# LDO.net
KiCad netlist of a schematic drawn in Altium Designer
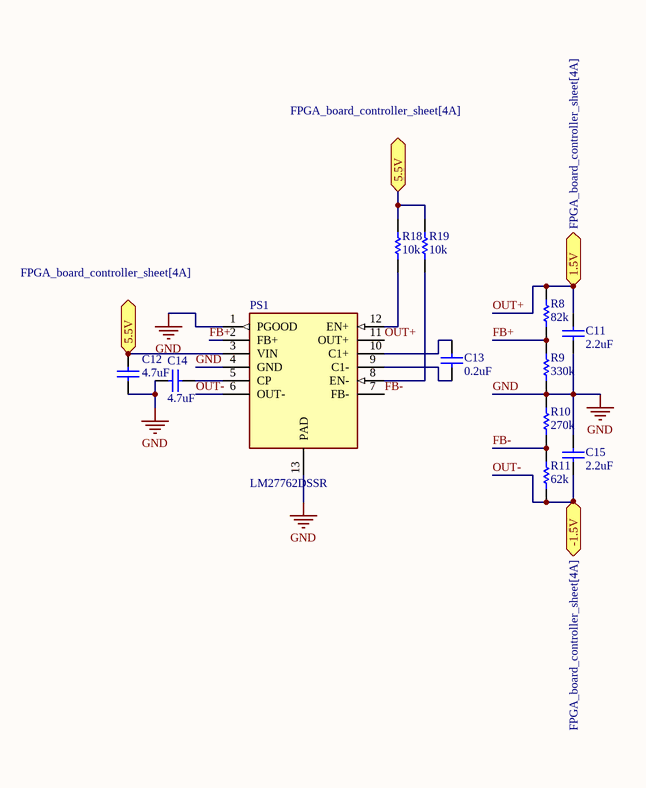
[diagram p0: LDO.SchDoc]

(export (version "E")
  (design (tool "Eeschema 10.0.6"))
  (components
    (comp (ref "C11")
      (value "2.2uF")
      (footprint "C0603")
      (libsource (lib "Schlib_FPGA_Controller") (part "Cap"))
    )
    (comp (ref "C12")
      (value "4.7uF")
      (footprint "C0603")
      (libsource (lib "Schlib_FPGA_Controller") (part "Cap"))
    )
    (comp (ref "C13")
      (value "0.2uF")
      (footprint "C0603")
      (libsource (lib "Schlib_FPGA_Controller") (part "Cap"))
    )
    (comp (ref "C14")
      (value "4.7uF")
      (footprint "C0603")
      (libsource (lib "Schlib_FPGA_Controller") (part "Cap"))
    )
    (comp (ref "C15")
      (value "2.2uF")
      (footprint "C0603")
      (libsource (lib "Schlib_FPGA_Controller") (part "Cap"))
    )
    (comp (ref "PS1")
      (value "LM27762DSSR")
      (footprint "SamacSys:SON50P200X300X80-13N-D")
      (description "Power Supply")
      (fields (field (name "MOUSER PART NUMBER") "595-LM27762DSSR"))
      (libsource (lib "Schlib_FPGA_Controller") (part "LM27762DSSR"))
    )
    (comp (ref "R8")
      (value "82k")
      (footprint "R0603")
      (libsource (lib "Schlib_FPGA_Controller") (part "Resistor"))
    )
    (comp (ref "R9")
      (value "330k")
      (footprint "R0603")
      (libsource (lib "Schlib_FPGA_Controller") (part "Resistor"))
    )
    (comp (ref "R10")
      (value "270k")
      (footprint "R0603")
      (libsource (lib "Schlib_FPGA_Controller") (part "Resistor"))
    )
    (comp (ref "R11")
      (value "62k")
      (footprint "R0603")
      (libsource (lib "Schlib_FPGA_Controller") (part "Resistor"))
    )
    (comp (ref "R18")
      (value "10k")
      (footprint "R0603")
      (libsource (lib "Schlib_FPGA_Controller") (part "Resistor"))
    )
    (comp (ref "R19")
      (value "10k")
      (footprint "R0603")
      (libsource (lib "Schlib_FPGA_Controller") (part "Resistor"))
    )
  )
  (nets
    (net (code "1") (name "/5.5V") (class "Default")
      (node (ref "C12") (pin "2") (pinfunction "2_2") (pintype "passive"))
      (node (ref "PS1") (pin "3") (pinfunction "VIN_3") (pintype "power_in"))
      (node (ref "R18") (pin "2") (pinfunction "2_2") (pintype "passive"))
      (node (ref "R19") (pin "2") (pinfunction "2_2") (pintype "passive"))
    )
    (net (code "2") (name "/FB+") (class "Default")
      (node (ref "PS1") (pin "2") (pinfunction "FB+_2") (pintype "power_in"))
      (node (ref "R8") (pin "1") (pinfunction "1_1") (pintype "passive"))
      (node (ref "R9") (pin "2") (pinfunction "2_2") (pintype "passive"))
    )
    (net (code "3") (name "/FB-") (class "Default")
      (node (ref "PS1") (pin "7") (pinfunction "FB-_7") (pintype "power_in"))
      (node (ref "R10") (pin "1") (pinfunction "1_1") (pintype "passive"))
      (node (ref "R11") (pin "2") (pinfunction "2_2") (pintype "passive"))
    )
    (net (code "4") (name "/OUT+") (class "Default")
      (node (ref "C11") (pin "2") (pinfunction "2_2") (pintype "passive"))
      (node (ref "PS1") (pin "11") (pinfunction "OUT+_11") (pintype "power_in"))
      (node (ref "R8") (pin "2") (pinfunction "2_2") (pintype "passive"))
    )
    (net (code "5") (name "/OUT-") (class "Default")
      (node (ref "C15") (pin "1") (pinfunction "1_1") (pintype "passive"))
      (node (ref "PS1") (pin "6") (pinfunction "OUT-_6") (pintype "power_in"))
      (node (ref "R11") (pin "1") (pinfunction "1_1") (pintype "passive"))
    )
    (net (code "6") (name "GND") (class "Default")
      (node (ref "C11") (pin "1") (pinfunction "1_1") (pintype "passive"))
      (node (ref "C12") (pin "1") (pinfunction "1_1") (pintype "passive"))
      (node (ref "C14") (pin "1") (pinfunction "1_1") (pintype "passive"))
      (node (ref "C15") (pin "2") (pinfunction "2_2") (pintype "passive"))
      (node (ref "PS1") (pin "1") (pinfunction "PGOOD_1") (pintype "output"))
      (node (ref "PS1") (pin "13") (pinfunction "PAD_13") (pintype "power_in"))
      (node (ref "PS1") (pin "4") (pinfunction "GND_4") (pintype "power_in"))
      (node (ref "R10") (pin "2") (pinfunction "2_2") (pintype "passive"))
      (node (ref "R9") (pin "1") (pinfunction "1_1") (pintype "passive"))
    )
    (net (code "7") (name "Net-(PS1-C1+)") (class "Default")
      (node (ref "C13") (pin "2") (pinfunction "2_2") (pintype "passive"))
      (node (ref "PS1") (pin "10") (pinfunction "C1+_10") (pintype "power_in"))
    )
    (net (code "8") (name "Net-(PS1-C1-)") (class "Default")
      (node (ref "C13") (pin "1") (pinfunction "1_1") (pintype "passive"))
      (node (ref "PS1") (pin "9") (pinfunction "C1-_9") (pintype "power_in"))
    )
    (net (code "9") (name "Net-(PS1-CP)") (class "Default")
      (node (ref "C14") (pin "2") (pinfunction "2_2") (pintype "passive"))
      (node (ref "PS1") (pin "5") (pinfunction "CP_5") (pintype "power_in"))
    )
    (net (code "10") (name "Net-(PS1-EN+)") (class "Default")
      (node (ref "PS1") (pin "12") (pinfunction "EN+_12") (pintype "input"))
      (node (ref "R18") (pin "1") (pinfunction "1_1") (pintype "passive"))
    )
    (net (code "11") (name "Net-(PS1-EN-)") (class "Default")
      (node (ref "PS1") (pin "8") (pinfunction "EN-_8") (pintype "input"))
      (node (ref "R19") (pin "1") (pinfunction "1_1") (pintype "passive"))
    )
  )
)
